# Power.net
KiCad netlist of a schematic drawn in Altium Designer
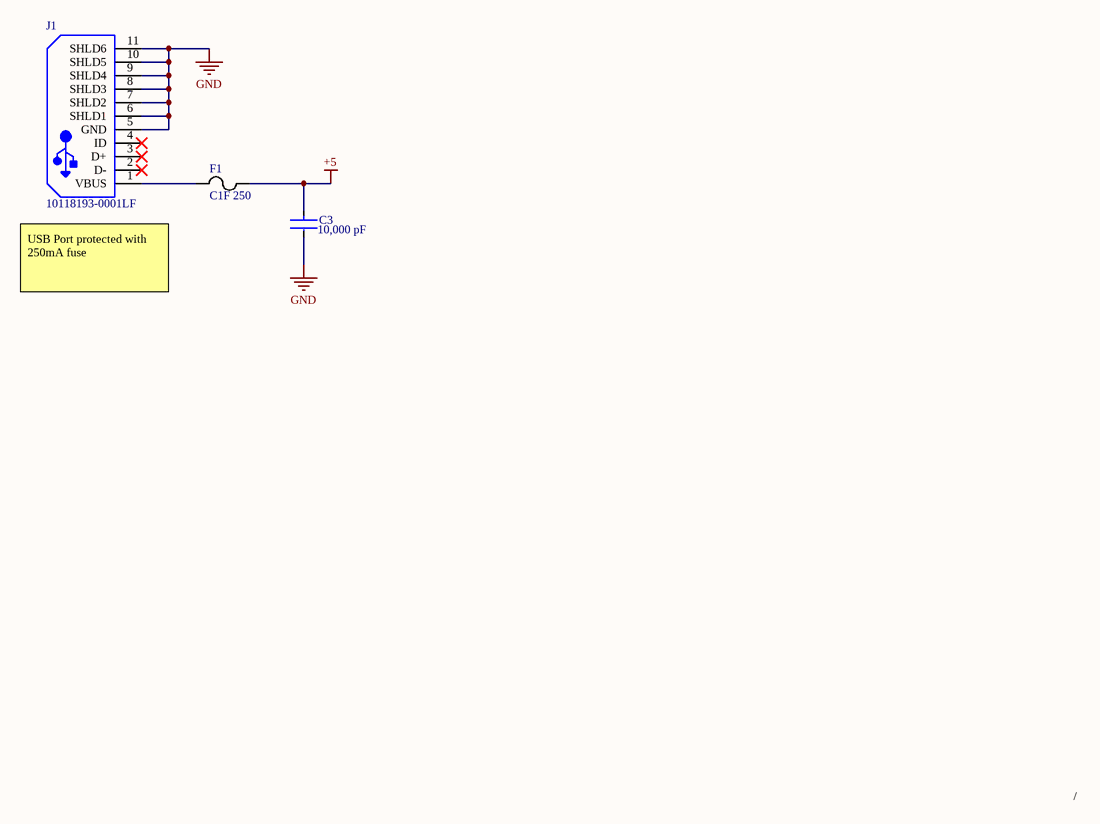
[diagram p0: Power.SchDoc]

(export (version "E")
  (design (tool "Eeschema 10.0.6"))
  (components
    (comp (ref "C3")
      (value "C1206C103K5RAC7210")
      (footprint "FP-C1206C-EB-MFG")
      (description "C1206 10,000 pF X7R 10.00% 50 V")
      (fields (field (name "TOLERANCE") "0.1") (field (name "CAPACITANCE") "10,000 pF"))
      (libsource (lib "Altium Content Vault") (part "b4654b650e69147ec39a6b967a45e02"))
    )
    (comp (ref "F1")
      (value "C1F 250")
      (footprint "C1_BEL")
      (description "Description")
      (fields (field (name "COPYRIGHT") "Copyright (C) 2026 Ultra Librarian. All rights reserved."))
      (libsource (lib "TutorialLibrary") (part "C1F 250"))
    )
    (comp (ref "J1")
      (value "10118193-0001LF")
      (footprint "FCI-10118193-0001LF-5_V")
      (description "Micro USB B Type Receptacle, -55 to 85 degC, 5-Pin SMD, RoHS, Tape and Reel")
      (fields (field (name "MANUFACTURER") "FCI"))
      (libsource (lib "Altium Content Vault") (part "USB-5-6SHLD"))
    )
  )
  (nets
    (net (code "1") (name "+5") (class "Default")
      (node (ref "C3") (pin "1") (pinfunction "1_1") (pintype "passive"))
      (node (ref "F1") (pin "2") (pinfunction "2_2") (pintype "passive"))
    )
    (net (code "2") (name "GND") (class "Default")
      (node (ref "C3") (pin "2") (pinfunction "2_2") (pintype "passive"))
      (node (ref "J1") (pin "10") (pinfunction "SHLD5_10") (pintype "passive"))
      (node (ref "J1") (pin "11") (pinfunction "SHLD6_11") (pintype "passive"))
      (node (ref "J1") (pin "5") (pinfunction "GND_5") (pintype "passive"))
      (node (ref "J1") (pin "6") (pinfunction "SHLD1_6") (pintype "passive"))
      (node (ref "J1") (pin "7") (pinfunction "SHLD2_7") (pintype "passive"))
      (node (ref "J1") (pin "8") (pinfunction "SHLD3_8") (pintype "passive"))
      (node (ref "J1") (pin "9") (pinfunction "SHLD4_9") (pintype "passive"))
    )
    (net (code "3") (name "Net-(J1-VBUS)") (class "Default")
      (node (ref "F1") (pin "1") (pinfunction "1_1") (pintype "passive"))
      (node (ref "J1") (pin "1") (pinfunction "VBUS_1") (pintype "passive"))
    )
    (net (code "4") (name "unconnected-(J1-D+-Pad3)") (class "Default")
      (node (ref "J1") (pin "3") (pinfunction "D+_3") (pintype "passive+no_connect"))
    )
    (net (code "5") (name "unconnected-(J1-D--Pad2)") (class "Default")
      (node (ref "J1") (pin "2") (pinfunction "D-_2") (pintype "passive+no_connect"))
    )
    (net (code "6") (name "unconnected-(J1-ID-Pad4)") (class "Default")
      (node (ref "J1") (pin "4") (pinfunction "ID_4") (pintype "passive+no_connect"))
    )
  )
)
